# Arduino_Mega14x.net
KiCad netlist of a schematic drawn in EAGLE
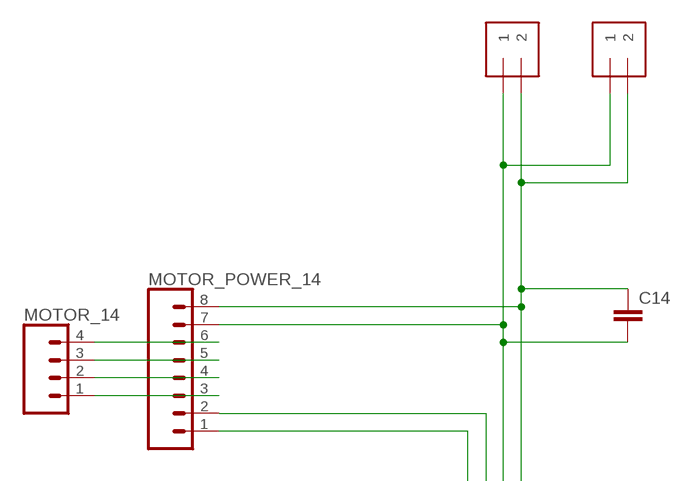
[diagram p0: schematic, sheet 1, part 1 of 3]
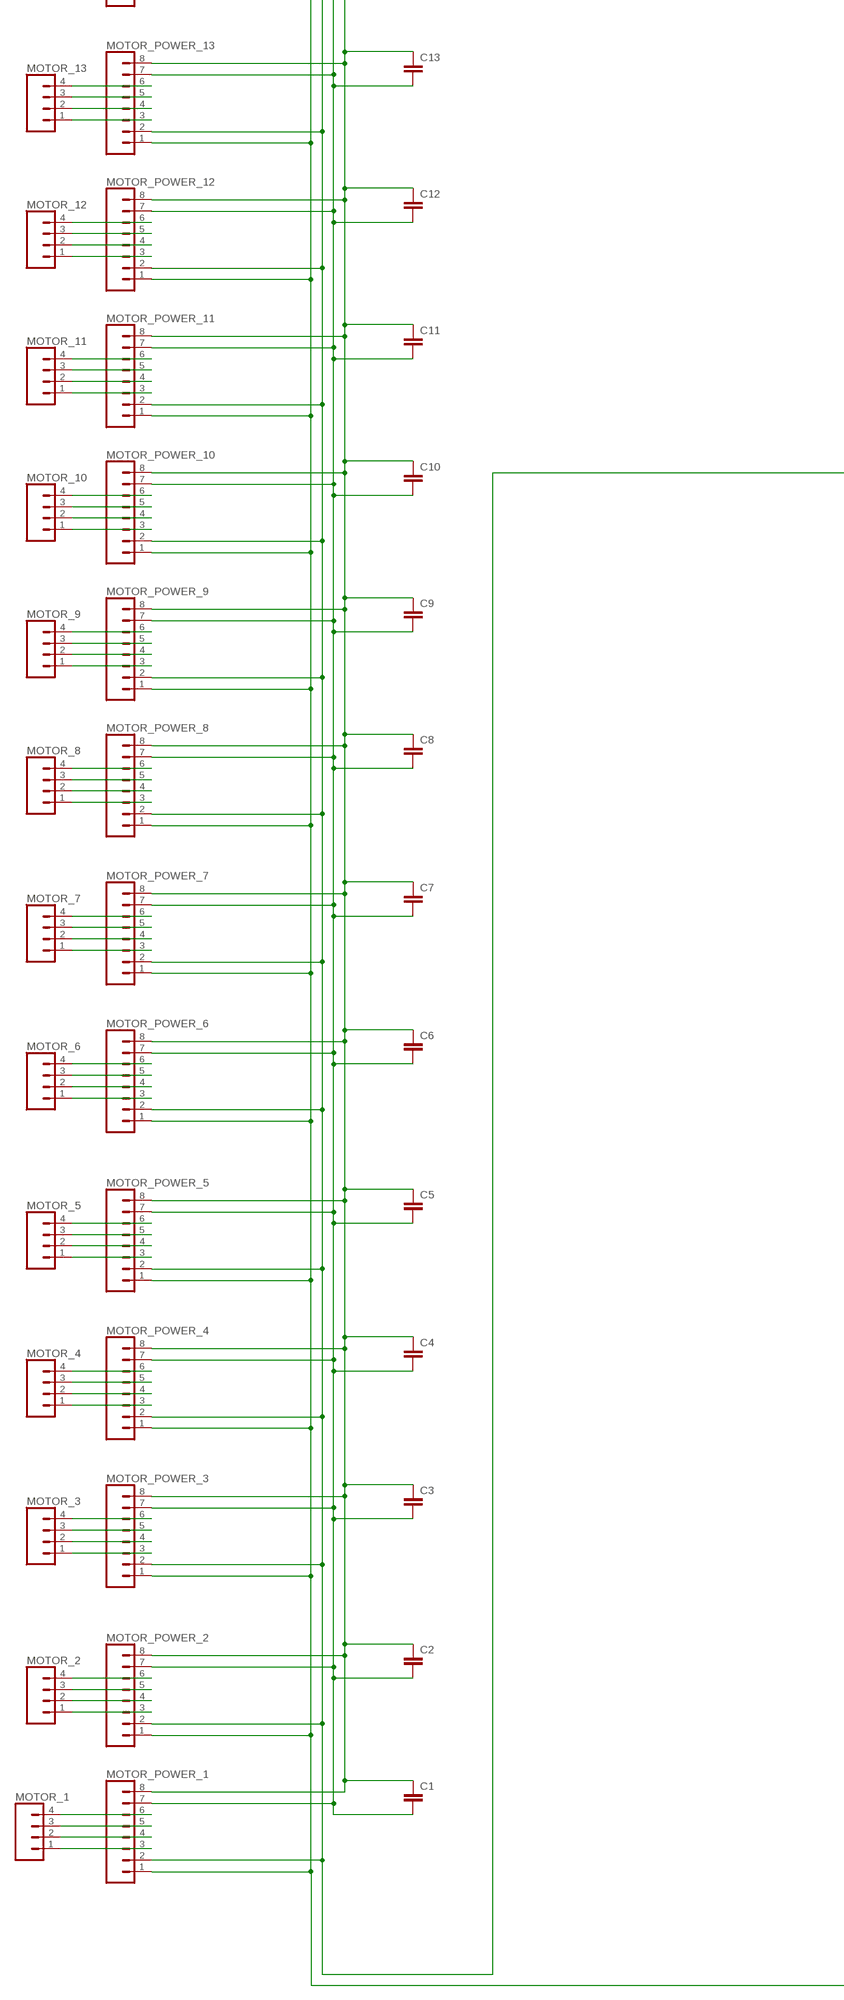
[diagram p1: schematic, sheet 1, part 2 of 3]
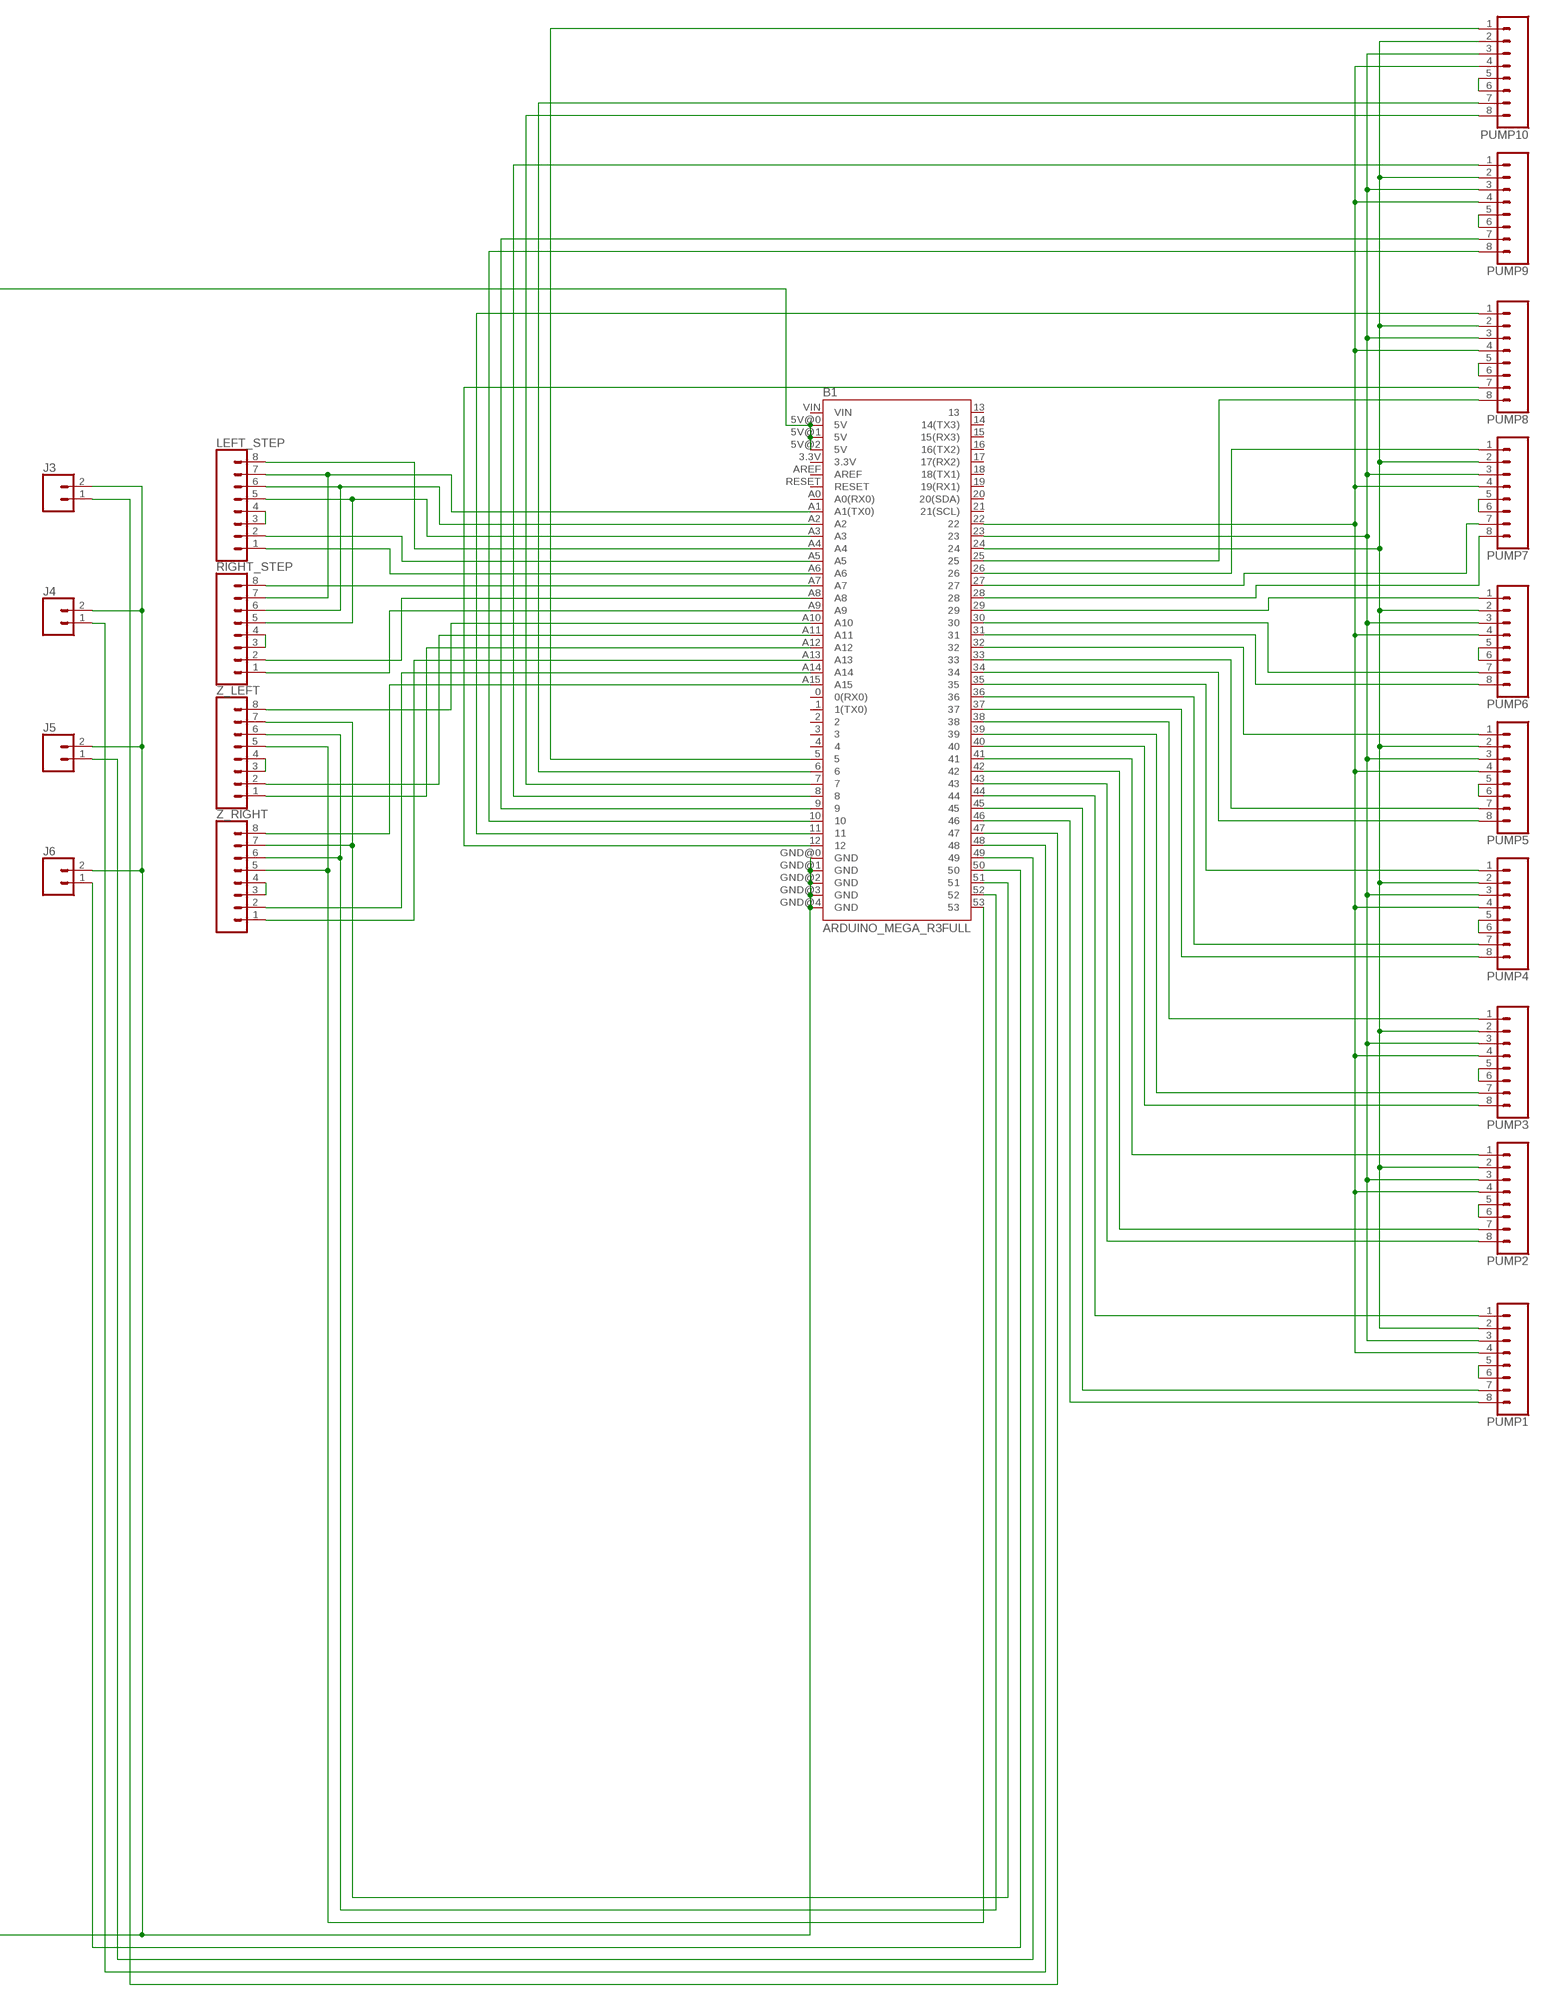
[diagram p2: schematic, sheet 1, part 3 of 3]

(export (version "E")
  (design (tool "Eeschema 10.0.6"))
  (components
    (comp (ref "B1")
      (value "ARDUINO_MEGA_R3FULL")
      (footprint "eagle-import:ARDUINO_MEGA")
      (libsource (lib "eagle-import") (part "ARDUINO_MEGA_R3FULL"))
    )
    (comp (ref "C1")
      (value "C5/2.5")
      (footprint "eagle-import:C5B2.5")
      (libsource (lib "eagle-import") (part "C5/2.5"))
    )
    (comp (ref "C2")
      (value "C5/2.5")
      (footprint "eagle-import:C5B2.5")
      (libsource (lib "eagle-import") (part "C5/2.5"))
    )
    (comp (ref "C3")
      (value "C5/2.5")
      (footprint "eagle-import:C5B2.5")
      (libsource (lib "eagle-import") (part "C5/2.5"))
    )
    (comp (ref "C4")
      (value "C5/2.5")
      (footprint "eagle-import:C5B2.5")
      (libsource (lib "eagle-import") (part "C5/2.5"))
    )
    (comp (ref "C5")
      (value "C5/2.5")
      (footprint "eagle-import:C5B2.5")
      (libsource (lib "eagle-import") (part "C5/2.5"))
    )
    (comp (ref "C6")
      (value "C5/2.5")
      (footprint "eagle-import:C5B2.5")
      (libsource (lib "eagle-import") (part "C5/2.5"))
    )
    (comp (ref "C7")
      (value "C5/2.5")
      (footprint "eagle-import:C5B2.5")
      (libsource (lib "eagle-import") (part "C5/2.5"))
    )
    (comp (ref "C8")
      (value "C5/2.5")
      (footprint "eagle-import:C5B2.5")
      (libsource (lib "eagle-import") (part "C5/2.5"))
    )
    (comp (ref "C9")
      (value "C5/2.5")
      (footprint "eagle-import:C5B2.5")
      (libsource (lib "eagle-import") (part "C5/2.5"))
    )
    (comp (ref "C10")
      (value "C5/2.5")
      (footprint "eagle-import:C5B2.5")
      (libsource (lib "eagle-import") (part "C5/2.5"))
    )
    (comp (ref "C11")
      (value "C5/2.5")
      (footprint "eagle-import:C5B2.5")
      (libsource (lib "eagle-import") (part "C5/2.5"))
    )
    (comp (ref "C12")
      (value "C5/2.5")
      (footprint "eagle-import:C5B2.5")
      (libsource (lib "eagle-import") (part "C5/2.5"))
    )
    (comp (ref "C13")
      (value "C5/2.5")
      (footprint "eagle-import:C5B2.5")
      (libsource (lib "eagle-import") (part "C5/2.5"))
    )
    (comp (ref "C14")
      (value "C5/2.5")
      (footprint "eagle-import:C5B2.5")
      (libsource (lib "eagle-import") (part "C5/2.5"))
    )
    (comp (ref "J1")
      (value "1X2-3.5MM")
      (footprint "eagle-import:1X2-3.5MM")
      (libsource (lib "eagle-import") (part "1X2-3.5MM"))
    )
    (comp (ref "J2")
      (value "1X2-3.5MM")
      (footprint "eagle-import:1X2-3.5MM")
      (libsource (lib "eagle-import") (part "1X2-3.5MM"))
    )
    (comp (ref "J3")
      (value "CONN_02")
      (footprint "eagle-import:1X02")
      (libsource (lib "eagle-import") (part "CONN_02"))
    )
    (comp (ref "J4")
      (value "CONN_02")
      (footprint "eagle-import:1X02")
      (libsource (lib "eagle-import") (part "CONN_02"))
    )
    (comp (ref "J5")
      (value "CONN_02")
      (footprint "eagle-import:1X02")
      (libsource (lib "eagle-import") (part "CONN_02"))
    )
    (comp (ref "J6")
      (value "CONN_02")
      (footprint "eagle-import:1X02")
      (libsource (lib "eagle-import") (part "CONN_02"))
    )
    (comp (ref "LEFT_STEP")
      (value "CONN_08\"")
      (footprint "eagle-import:1X08")
      (libsource (lib "eagle-import") (part "CONN_08{dblquote}"))
    )
    (comp (ref "MOTOR_1")
      (value "CONN_04")
      (footprint "eagle-import:1X04")
      (libsource (lib "eagle-import") (part "CONN_04"))
    )
    (comp (ref "MOTOR_2")
      (value "CONN_04")
      (footprint "eagle-import:1X04")
      (libsource (lib "eagle-import") (part "CONN_04"))
    )
    (comp (ref "MOTOR_3")
      (value "CONN_04")
      (footprint "eagle-import:1X04")
      (libsource (lib "eagle-import") (part "CONN_04"))
    )
    (comp (ref "MOTOR_4")
      (value "CONN_04")
      (footprint "eagle-import:1X04")
      (libsource (lib "eagle-import") (part "CONN_04"))
    )
    (comp (ref "MOTOR_5")
      (value "CONN_04")
      (footprint "eagle-import:1X04")
      (libsource (lib "eagle-import") (part "CONN_04"))
    )
    (comp (ref "MOTOR_6")
      (value "CONN_04")
      (footprint "eagle-import:1X04")
      (libsource (lib "eagle-import") (part "CONN_04"))
    )
    (comp (ref "MOTOR_7")
      (value "CONN_04")
      (footprint "eagle-import:1X04")
      (libsource (lib "eagle-import") (part "CONN_04"))
    )
    (comp (ref "MOTOR_8")
      (value "CONN_04")
      (footprint "eagle-import:1X04")
      (libsource (lib "eagle-import") (part "CONN_04"))
    )
    (comp (ref "MOTOR_9")
      (value "CONN_04")
      (footprint "eagle-import:1X04")
      (libsource (lib "eagle-import") (part "CONN_04"))
    )
    (comp (ref "MOTOR_10")
      (value "CONN_04")
      (footprint "eagle-import:1X04")
      (libsource (lib "eagle-import") (part "CONN_04"))
    )
    (comp (ref "MOTOR_11")
      (value "CONN_04")
      (footprint "eagle-import:1X04")
      (libsource (lib "eagle-import") (part "CONN_04"))
    )
    (comp (ref "MOTOR_12")
      (value "CONN_04")
      (footprint "eagle-import:1X04")
      (libsource (lib "eagle-import") (part "CONN_04"))
    )
    (comp (ref "MOTOR_13")
      (value "CONN_04")
      (footprint "eagle-import:1X04")
      (libsource (lib "eagle-import") (part "CONN_04"))
    )
    (comp (ref "MOTOR_14")
      (value "CONN_04")
      (footprint "eagle-import:1X04")
      (libsource (lib "eagle-import") (part "CONN_04"))
    )
    (comp (ref "MOTOR_POWER_1")
      (value "CONN_08\"")
      (footprint "eagle-import:1X08")
      (libsource (lib "eagle-import") (part "CONN_08{dblquote}"))
    )
    (comp (ref "MOTOR_POWER_2")
      (value "CONN_08\"")
      (footprint "eagle-import:1X08")
      (libsource (lib "eagle-import") (part "CONN_08{dblquote}"))
    )
    (comp (ref "MOTOR_POWER_3")
      (value "CONN_08\"")
      (footprint "eagle-import:1X08")
      (libsource (lib "eagle-import") (part "CONN_08{dblquote}"))
    )
    (comp (ref "MOTOR_POWER_4")
      (value "CONN_08\"")
      (footprint "eagle-import:1X08")
      (libsource (lib "eagle-import") (part "CONN_08{dblquote}"))
    )
    (comp (ref "MOTOR_POWER_5")
      (value "CONN_08\"")
      (footprint "eagle-import:1X08")
      (libsource (lib "eagle-import") (part "CONN_08{dblquote}"))
    )
    (comp (ref "MOTOR_POWER_6")
      (value "CONN_08\"")
      (footprint "eagle-import:1X08")
      (libsource (lib "eagle-import") (part "CONN_08{dblquote}"))
    )
    (comp (ref "MOTOR_POWER_7")
      (value "CONN_08\"")
      (footprint "eagle-import:1X08")
      (libsource (lib "eagle-import") (part "CONN_08{dblquote}"))
    )
    (comp (ref "MOTOR_POWER_8")
      (value "CONN_08\"")
      (footprint "eagle-import:1X08")
      (libsource (lib "eagle-import") (part "CONN_08{dblquote}"))
    )
    (comp (ref "MOTOR_POWER_9")
      (value "CONN_08\"")
      (footprint "eagle-import:1X08")
      (libsource (lib "eagle-import") (part "CONN_08{dblquote}"))
    )
    (comp (ref "MOTOR_POWER_10")
      (value "CONN_08\"")
      (footprint "eagle-import:1X08")
      (libsource (lib "eagle-import") (part "CONN_08{dblquote}"))
    )
    (comp (ref "MOTOR_POWER_11")
      (value "CONN_08\"")
      (footprint "eagle-import:1X08")
      (libsource (lib "eagle-import") (part "CONN_08{dblquote}"))
    )
    (comp (ref "MOTOR_POWER_12")
      (value "CONN_08\"")
      (footprint "eagle-import:1X08")
      (libsource (lib "eagle-import") (part "CONN_08{dblquote}"))
    )
    (comp (ref "MOTOR_POWER_13")
      (value "CONN_08\"")
      (footprint "eagle-import:1X08")
      (libsource (lib "eagle-import") (part "CONN_08{dblquote}"))
    )
    (comp (ref "MOTOR_POWER_14")
      (value "CONN_08\"")
      (footprint "eagle-import:1X08")
      (libsource (lib "eagle-import") (part "CONN_08{dblquote}"))
    )
    (comp (ref "PUMP1")
      (value "CONN_08\"")
      (footprint "eagle-import:1X08")
      (libsource (lib "eagle-import") (part "CONN_08{dblquote}"))
    )
    (comp (ref "PUMP2")
      (value "CONN_08\"")
      (footprint "eagle-import:1X08")
      (libsource (lib "eagle-import") (part "CONN_08{dblquote}"))
    )
    (comp (ref "PUMP3")
      (value "CONN_08\"")
      (footprint "eagle-import:1X08")
      (libsource (lib "eagle-import") (part "CONN_08{dblquote}"))
    )
    (comp (ref "PUMP4")
      (value "CONN_08\"")
      (footprint "eagle-import:1X08")
      (libsource (lib "eagle-import") (part "CONN_08{dblquote}"))
    )
    (comp (ref "PUMP5")
      (value "CONN_08\"")
      (footprint "eagle-import:1X08")
      (libsource (lib "eagle-import") (part "CONN_08{dblquote}"))
    )
    (comp (ref "PUMP6")
      (value "CONN_08\"")
      (footprint "eagle-import:1X08")
      (libsource (lib "eagle-import") (part "CONN_08{dblquote}"))
    )
    (comp (ref "PUMP7")
      (value "CONN_08\"")
      (footprint "eagle-import:1X08")
      (libsource (lib "eagle-import") (part "CONN_08{dblquote}"))
    )
    (comp (ref "PUMP8")
      (value "CONN_08\"")
      (footprint "eagle-import:1X08")
      (libsource (lib "eagle-import") (part "CONN_08{dblquote}"))
    )
    (comp (ref "PUMP9")
      (value "CONN_08\"")
      (footprint "eagle-import:1X08")
      (libsource (lib "eagle-import") (part "CONN_08{dblquote}"))
    )
    (comp (ref "PUMP10")
      (value "CONN_08\"")
      (footprint "eagle-import:1X08")
      (libsource (lib "eagle-import") (part "CONN_08{dblquote}"))
    )
    (comp (ref "RIGHT_STEP")
      (value "CONN_08\"")
      (footprint "eagle-import:1X08")
      (libsource (lib "eagle-import") (part "CONN_08{dblquote}"))
    )
    (comp (ref "Z_LEFT")
      (value "CONN_08\"")
      (footprint "eagle-import:1X08")
      (libsource (lib "eagle-import") (part "CONN_08{dblquote}"))
    )
    (comp (ref "Z_RIGHT")
      (value "CONN_08\"")
      (footprint "eagle-import:1X08")
      (libsource (lib "eagle-import") (part "CONN_08{dblquote}"))
    )
  )
  (nets
    (net (code "1") (name "Net-(B1-5V-Pad5V@0)") (class "Default")
      (node (ref "B1") (pin "5V@0") (pinfunction "5V_5V@0") (pintype "bidirectional"))
      (node (ref "B1") (pin "5V@1") (pinfunction "5V_5V@1") (pintype "bidirectional"))
      (node (ref "B1") (pin "5V@2") (pinfunction "5V_5V@2") (pintype "bidirectional"))
      (node (ref "MOTOR_POWER_1") (pin "2") (pinfunction "2_2") (pintype "passive"))
      (node (ref "MOTOR_POWER_10") (pin "2") (pinfunction "2_2") (pintype "passive"))
      (node (ref "MOTOR_POWER_11") (pin "2") (pinfunction "2_2") (pintype "passive"))
      (node (ref "MOTOR_POWER_12") (pin "2") (pinfunction "2_2") (pintype "passive"))
      (node (ref "MOTOR_POWER_13") (pin "2") (pinfunction "2_2") (pintype "passive"))
      (node (ref "MOTOR_POWER_14") (pin "2") (pinfunction "2_2") (pintype "passive"))
      (node (ref "MOTOR_POWER_2") (pin "2") (pinfunction "2_2") (pintype "passive"))
      (node (ref "MOTOR_POWER_3") (pin "2") (pinfunction "2_2") (pintype "passive"))
      (node (ref "MOTOR_POWER_4") (pin "2") (pinfunction "2_2") (pintype "passive"))
      (node (ref "MOTOR_POWER_5") (pin "2") (pinfunction "2_2") (pintype "passive"))
      (node (ref "MOTOR_POWER_6") (pin "2") (pinfunction "2_2") (pintype "passive"))
      (node (ref "MOTOR_POWER_7") (pin "2") (pinfunction "2_2") (pintype "passive"))
      (node (ref "MOTOR_POWER_8") (pin "2") (pinfunction "2_2") (pintype "passive"))
      (node (ref "MOTOR_POWER_9") (pin "2") (pinfunction "2_2") (pintype "passive"))
    )
    (net (code "2") (name "Net-(B1-A1(TX0))") (class "Default")
      (node (ref "B1") (pin "A1") (pinfunction "A1(TX0)_A1") (pintype "bidirectional"))
      (node (ref "LEFT_STEP") (pin "7") (pinfunction "7_7") (pintype "passive"))
      (node (ref "RIGHT_STEP") (pin "7") (pinfunction "7_7") (pintype "passive"))
    )
    (net (code "3") (name "Net-(B1-GND-PadGND@0)") (class "Default")
      (node (ref "B1") (pin "GND@0") (pinfunction "GND_GND@0") (pintype "bidirectional"))
      (node (ref "B1") (pin "GND@1") (pinfunction "GND_GND@1") (pintype "bidirectional"))
      (node (ref "B1") (pin "GND@2") (pinfunction "GND_GND@2") (pintype "bidirectional"))
      (node (ref "B1") (pin "GND@3") (pinfunction "GND_GND@3") (pintype "bidirectional"))
      (node (ref "B1") (pin "GND@4") (pinfunction "GND_GND@4") (pintype "bidirectional"))
      (node (ref "J3") (pin "2") (pinfunction "2_2") (pintype "passive"))
      (node (ref "J4") (pin "2") (pinfunction "2_2") (pintype "passive"))
      (node (ref "J5") (pin "2") (pinfunction "2_2") (pintype "passive"))
      (node (ref "J6") (pin "2") (pinfunction "2_2") (pintype "passive"))
      (node (ref "MOTOR_POWER_1") (pin "1") (pinfunction "1_1") (pintype "passive"))
      (node (ref "MOTOR_POWER_10") (pin "1") (pinfunction "1_1") (pintype "passive"))
      (node (ref "MOTOR_POWER_11") (pin "1") (pinfunction "1_1") (pintype "passive"))
      (node (ref "MOTOR_POWER_12") (pin "1") (pinfunction "1_1") (pintype "passive"))
      (node (ref "MOTOR_POWER_13") (pin "1") (pinfunction "1_1") (pintype "passive"))
      (node (ref "MOTOR_POWER_14") (pin "1") (pinfunction "1_1") (pintype "passive"))
      (node (ref "MOTOR_POWER_2") (pin "1") (pinfunction "1_1") (pintype "passive"))
      (node (ref "MOTOR_POWER_3") (pin "1") (pinfunction "1_1") (pintype "passive"))
      (node (ref "MOTOR_POWER_4") (pin "1") (pinfunction "1_1") (pintype "passive"))
      (node (ref "MOTOR_POWER_5") (pin "1") (pinfunction "1_1") (pintype "passive"))
      (node (ref "MOTOR_POWER_6") (pin "1") (pinfunction "1_1") (pintype "passive"))
      (node (ref "MOTOR_POWER_7") (pin "1") (pinfunction "1_1") (pintype "passive"))
      (node (ref "MOTOR_POWER_8") (pin "1") (pinfunction "1_1") (pintype "passive"))
      (node (ref "MOTOR_POWER_9") (pin "1") (pinfunction "1_1") (pintype "passive"))
    )
    (net (code "4") (name "Net-(B1-Pad5)") (class "Default")
      (node (ref "B1") (pin "5") (pinfunction "5_5") (pintype "bidirectional"))
      (node (ref "PUMP10") (pin "1") (pinfunction "1_1") (pintype "passive"))
    )
    (net (code "5") (name "Net-(B1-Pad6)") (class "Default")
      (node (ref "B1") (pin "6") (pinfunction "6_6") (pintype "bidirectional"))
      (node (ref "PUMP10") (pin "7") (pinfunction "7_7") (pintype "passive"))
    )
    (net (code "6") (name "Net-(B1-Pad7)") (class "Default")
      (node (ref "B1") (pin "7") (pinfunction "7_7") (pintype "bidirectional"))
      (node (ref "PUMP10") (pin "8") (pinfunction "8_8") (pintype "passive"))
    )
    (net (code "7") (name "Net-(B1-Pad8)") (class "Default")
      (node (ref "B1") (pin "8") (pinfunction "8_8") (pintype "bidirectional"))
      (node (ref "PUMP9") (pin "1") (pinfunction "1_1") (pintype "passive"))
    )
    (net (code "8") (name "Net-(B1-Pad9)") (class "Default")
      (node (ref "B1") (pin "9") (pinfunction "9_9") (pintype "bidirectional"))
      (node (ref "PUMP9") (pin "7") (pinfunction "7_7") (pintype "passive"))
    )
    (net (code "9") (name "Net-(B1-Pad10)") (class "Default")
      (node (ref "B1") (pin "10") (pinfunction "10_10") (pintype "bidirectional"))
      (node (ref "PUMP9") (pin "8") (pinfunction "8_8") (pintype "passive"))
    )
    (net (code "10") (name "Net-(B1-Pad11)") (class "Default")
      (node (ref "B1") (pin "11") (pinfunction "11_11") (pintype "bidirectional"))
      (node (ref "PUMP8") (pin "1") (pinfunction "1_1") (pintype "passive"))
    )
    (net (code "11") (name "Net-(B1-Pad12)") (class "Default")
      (node (ref "B1") (pin "12") (pinfunction "12_12") (pintype "bidirectional"))
      (node (ref "PUMP8") (pin "7") (pinfunction "7_7") (pintype "passive"))
    )
    (net (code "12") (name "Net-(B1-Pad22)") (class "Default")
      (node (ref "B1") (pin "22") (pinfunction "22_22") (pintype "bidirectional"))
      (node (ref "PUMP1") (pin "4") (pinfunction "4_4") (pintype "passive"))
      (node (ref "PUMP10") (pin "4") (pinfunction "4_4") (pintype "passive"))
      (node (ref "PUMP2") (pin "4") (pinfunction "4_4") (pintype "passive"))
      (node (ref "PUMP3") (pin "4") (pinfunction "4_4") (pintype "passive"))
      (node (ref "PUMP4") (pin "4") (pinfunction "4_4") (pintype "passive"))
      (node (ref "PUMP5") (pin "4") (pinfunction "4_4") (pintype "passive"))
      (node (ref "PUMP6") (pin "4") (pinfunction "4_4") (pintype "passive"))
      (node (ref "PUMP7") (pin "4") (pinfunction "4_4") (pintype "passive"))
      (node (ref "PUMP8") (pin "4") (pinfunction "4_4") (pintype "passive"))
      (node (ref "PUMP9") (pin "4") (pinfunction "4_4") (pintype "passive"))
    )
    (net (code "13") (name "Net-(B1-Pad23)") (class "Default")
      (node (ref "B1") (pin "23") (pinfunction "23_23") (pintype "bidirectional"))
      (node (ref "PUMP1") (pin "3") (pinfunction "3_3") (pintype "passive"))
      (node (ref "PUMP10") (pin "3") (pinfunction "3_3") (pintype "passive"))
      (node (ref "PUMP2") (pin "3") (pinfunction "3_3") (pintype "passive"))
      (node (ref "PUMP3") (pin "3") (pinfunction "3_3") (pintype "passive"))
      (node (ref "PUMP4") (pin "3") (pinfunction "3_3") (pintype "passive"))
      (node (ref "PUMP5") (pin "3") (pinfunction "3_3") (pintype "passive"))
      (node (ref "PUMP6") (pin "3") (pinfunction "3_3") (pintype "passive"))
      (node (ref "PUMP7") (pin "3") (pinfunction "3_3") (pintype "passive"))
      (node (ref "PUMP8") (pin "3") (pinfunction "3_3") (pintype "passive"))
      (node (ref "PUMP9") (pin "3") (pinfunction "3_3") (pintype "passive"))
    )
    (net (code "14") (name "Net-(B1-Pad24)") (class "Default")
      (node (ref "B1") (pin "24") (pinfunction "24_24") (pintype "bidirectional"))
      (node (ref "PUMP1") (pin "2") (pinfunction "2_2") (pintype "passive"))
      (node (ref "PUMP10") (pin "2") (pinfunction "2_2") (pintype "passive"))
      (node (ref "PUMP2") (pin "2") (pinfunction "2_2") (pintype "passive"))
      (node (ref "PUMP3") (pin "2") (pinfunction "2_2") (pintype "passive"))
      (node (ref "PUMP4") (pin "2") (pinfunction "2_2") (pintype "passive"))
      (node (ref "PUMP5") (pin "2") (pinfunction "2_2") (pintype "passive"))
      (node (ref "PUMP6") (pin "2") (pinfunction "2_2") (pintype "passive"))
      (node (ref "PUMP7") (pin "2") (pinfunction "2_2") (pintype "passive"))
      (node (ref "PUMP8") (pin "2") (pinfunction "2_2") (pintype "passive"))
      (node (ref "PUMP9") (pin "2") (pinfunction "2_2") (pintype "passive"))
    )
    (net (code "15") (name "Net-(B1-Pad25)") (class "Default")
      (node (ref "B1") (pin "25") (pinfunction "25_25") (pintype "bidirectional"))
      (node (ref "PUMP8") (pin "8") (pinfunction "8_8") (pintype "passive"))
    )
    (net (code "16") (name "Net-(B1-Pad26)") (class "Default")
      (node (ref "B1") (pin "26") (pinfunction "26_26") (pintype "bidirectional"))
      (node (ref "PUMP7") (pin "1") (pinfunction "1_1") (pintype "passive"))
    )
    (net (code "17") (name "Net-(B1-Pad27)") (class "Default")
      (node (ref "B1") (pin "27") (pinfunction "27_27") (pintype "bidirectional"))
      (node (ref "PUMP7") (pin "7") (pinfunction "7_7") (pintype "passive"))
    )
    (net (code "18") (name "Net-(B1-Pad28)") (class "Default")
      (node (ref "B1") (pin "28") (pinfunction "28_28") (pintype "bidirectional"))
      (node (ref "PUMP7") (pin "8") (pinfunction "8_8") (pintype "passive"))
    )
    (net (code "19") (name "Net-(B1-Pad29)") (class "Default")
      (node (ref "B1") (pin "29") (pinfunction "29_29") (pintype "bidirectional"))
      (node (ref "PUMP6") (pin "1") (pinfunction "1_1") (pintype "passive"))
    )
    (net (code "20") (name "Net-(B1-Pad30)") (class "Default")
      (node (ref "B1") (pin "30") (pinfunction "30_30") (pintype "bidirectional"))
      (node (ref "PUMP6") (pin "7") (pinfunction "7_7") (pintype "passive"))
    )
    (net (code "21") (name "Net-(B1-Pad31)") (class "Default")
      (node (ref "B1") (pin "31") (pinfunction "31_31") (pintype "bidirectional"))
      (node (ref "PUMP6") (pin "8") (pinfunction "8_8") (pintype "passive"))
    )
    (net (code "22") (name "Net-(B1-Pad32)") (class "Default")
      (node (ref "B1") (pin "32") (pinfunction "32_32") (pintype "bidirectional"))
      (node (ref "PUMP5") (pin "1") (pinfunction "1_1") (pintype "passive"))
    )
    (net (code "23") (name "Net-(B1-Pad33)") (class "Default")
      (node (ref "B1") (pin "33") (pinfunction "33_33") (pintype "bidirectional"))
      (node (ref "PUMP5") (pin "7") (pinfunction "7_7") (pintype "passive"))
    )
    (net (code "24") (name "Net-(B1-Pad34)") (class "Default")
      (node (ref "B1") (pin "34") (pinfunction "34_34") (pintype "bidirectional"))
      (node (ref "PUMP5") (pin "8") (pinfunction "8_8") (pintype "passive"))
    )
    (net (code "25") (name "Net-(B1-Pad35)") (class "Default")
      (node (ref "B1") (pin "35") (pinfunction "35_35") (pintype "bidirectional"))
      (node (ref "PUMP4") (pin "1") (pinfunction "1_1") (pintype "passive"))
    )
    (net (code "26") (name "Net-(B1-Pad36)") (class "Default")
      (node (ref "B1") (pin "36") (pinfunction "36_36") (pintype "bidirectional"))
      (node (ref "PUMP4") (pin "7") (pinfunction "7_7") (pintype "passive"))
    )
    (net (code "27") (name "Net-(B1-Pad37)") (class "Default")
      (node (ref "B1") (pin "37") (pinfunction "37_37") (pintype "bidirectional"))
      (node (ref "PUMP4") (pin "8") (pinfunction "8_8") (pintype "passive"))
    )
    (net (code "28") (name "Net-(B1-Pad38)") (class "Default")
      (node (ref "B1") (pin "38") (pinfunction "38_38") (pintype "bidirectional"))
      (node (ref "PUMP3") (pin "1") (pinfunction "1_1") (pintype "passive"))
    )
    (net (code "29") (name "Net-(B1-Pad39)") (class "Default")
      (node (ref "B1") (pin "39") (pinfunction "39_39") (pintype "bidirectional"))
      (node (ref "PUMP3") (pin "7") (pinfunction "7_7") (pintype "passive"))
    )
    (net (code "30") (name "Net-(B1-Pad40)") (class "Default")
      (node (ref "B1") (pin "40") (pinfunction "40_40") (pintype "bidirectional"))
      (node (ref "PUMP3") (pin "8") (pinfunction "8_8") (pintype "passive"))
    )
    (net (code "31") (name "Net-(B1-Pad41)") (class "Default")
      (node (ref "B1") (pin "41") (pinfunction "41_41") (pintype "bidirectional"))
      (node (ref "PUMP2") (pin "1") (pinfunction "1_1") (pintype "passive"))
    )
    (net (code "32") (name "Net-(B1-Pad42)") (class "Default")
      (node (ref "B1") (pin "42") (pinfunction "42_42") (pintype "bidirectional"))
      (node (ref "PUMP2") (pin "7") (pinfunction "7_7") (pintype "passive"))
    )
    (net (code "33") (name "Net-(B1-Pad43)") (class "Default")
      (node (ref "B1") (pin "43") (pinfunction "43_43") (pintype "bidirectional"))
      (node (ref "PUMP2") (pin "8") (pinfunction "8_8") (pintype "passive"))
    )
    (net (code "34") (name "Net-(B1-Pad44)") (class "Default")
      (node (ref "B1") (pin "44") (pinfunction "44_44") (pintype "bidirectional"))
      (node (ref "PUMP1") (pin "1") (pinfunction "1_1") (pintype "passive"))
    )
    (net (code "35") (name "Net-(B1-Pad45)") (class "Default")
      (node (ref "B1") (pin "45") (pinfunction "45_45") (pintype "bidirectional"))
      (node (ref "PUMP1") (pin "7") (pinfunction "7_7") (pintype "passive"))
    )
    (net (code "36") (name "Net-(B1-Pad46)") (class "Default")
      (node (ref "B1") (pin "46") (pinfunction "46_46") (pintype "bidirectional"))
      (node (ref "PUMP1") (pin "8") (pinfunction "8_8") (pintype "passive"))
    )
    (net (code "37") (name "Net-(B1-Pad47)") (class "Default")
      (node (ref "B1") (pin "47") (pinfunction "47_47") (pintype "bidirectional"))
      (node (ref "J3") (pin "1") (pinfunction "1_1") (pintype "passive"))
    )
    (net (code "38") (name "Net-(B1-Pad48)") (class "Default")
      (node (ref "B1") (pin "48") (pinfunction "48_48") (pintype "bidirectional"))
      (node (ref "J4") (pin "1") (pinfunction "1_1") (pintype "passive"))
    )
    (net (code "39") (name "Net-(B1-Pad49)") (class "Default")
      (node (ref "B1") (pin "49") (pinfunction "49_49") (pintype "bidirectional"))
      (node (ref "J5") (pin "1") (pinfunction "1_1") (pintype "passive"))
    )
    (net (code "40") (name "Net-(B1-Pad50)") (class "Default")
      (node (ref "B1") (pin "50") (pinfunction "50_50") (pintype "bidirectional"))
      (node (ref "J6") (pin "1") (pinfunction "1_1") (pintype "passive"))
    )
    (net (code "41") (name "Net-(B1-Pad51)") (class "Default")
      (node (ref "B1") (pin "51") (pinfunction "51_51") (pintype "bidirectional"))
      (node (ref "Z_LEFT") (pin "7") (pinfunction "7_7") (pintype "passive"))
      (node (ref "Z_RIGHT") (pin "7") (pinfunction "7_7") (pintype "passive"))
    )
    (net (code "42") (name "Net-(B1-Pad52)") (class "Default")
      (node (ref "B1") (pin "52") (pinfunction "52_52") (pintype "bidirectional"))
      (node (ref "Z_LEFT") (pin "6") (pinfunction "6_6") (pintype "passive"))
      (node (ref "Z_RIGHT") (pin "6") (pinfunction "6_6") (pintype "passive"))
    )
    (net (code "43") (name "Net-(B1-Pad53)") (class "Default")
      (node (ref "B1") (pin "53") (pinfunction "53_53") (pintype "bidirectional"))
      (node (ref "Z_LEFT") (pin "5") (pinfunction "5_5") (pintype "passive"))
      (node (ref "Z_RIGHT") (pin "5") (pinfunction "5_5") (pintype "passive"))
    )
    (net (code "44") (name "Net-(B1-PadA2)") (class "Default")
      (node (ref "B1") (pin "A2") (pinfunction "A2_A2") (pintype "bidirectional"))
      (node (ref "LEFT_STEP") (pin "6") (pinfunction "6_6") (pintype "passive"))
      (node (ref "RIGHT_STEP") (pin "6") (pinfunction "6_6") (pintype "passive"))
    )
    (net (code "45") (name "Net-(B1-PadA3)") (class "Default")
      (node (ref "B1") (pin "A3") (pinfunction "A3_A3") (pintype "bidirectional"))
      (node (ref "LEFT_STEP") (pin "5") (pinfunction "5_5") (pintype "passive"))
      (node (ref "RIGHT_STEP") (pin "5") (pinfunction "5_5") (pintype "passive"))
    )
    (net (code "46") (name "Net-(B1-PadA4)") (class "Default")
      (node (ref "B1") (pin "A4") (pinfunction "A4_A4") (pintype "bidirectional"))
      (node (ref "LEFT_STEP") (pin "8") (pinfunction "8_8") (pintype "passive"))
    )
    (net (code "47") (name "Net-(B1-PadA5)") (class "Default")
      (node (ref "B1") (pin "A5") (pinfunction "A5_A5") (pintype "bidirectional"))
      (node (ref "LEFT_STEP") (pin "2") (pinfunction "2_2") (pintype "passive"))
    )
    (net (code "48") (name "Net-(B1-PadA6)") (class "Default")
      (node (ref "B1") (pin "A6") (pinfunction "A6_A6") (pintype "bidirectional"))
      (node (ref "LEFT_STEP") (pin "1") (pinfunction "1_1") (pintype "passive"))
    )
    (net (code "49") (name "Net-(B1-PadA7)") (class "Default")
      (node (ref "B1") (pin "A7") (pinfunction "A7_A7") (pintype "bidirectional"))
      (node (ref "RIGHT_STEP") (pin "8") (pinfunction "8_8") (pintype "passive"))
    )
    (net (code "50") (name "Net-(B1-PadA8)") (class "Default")
      (node (ref "B1") (pin "A8") (pinfunction "A8_A8") (pintype "bidirectional"))
      (node (ref "RIGHT_STEP") (pin "2") (pinfunction "2_2") (pintype "passive"))
    )
    (net (code "51") (name "Net-(B1-PadA9)") (class "Default")
      (node (ref "B1") (pin "A9") (pinfunction "A9_A9") (pintype "bidirectional"))
      (node (ref "RIGHT_STEP") (pin "1") (pinfunction "1_1") (pintype "passive"))
    )
    (net (code "52") (name "Net-(B1-PadA10)") (class "Default")
      (node (ref "B1") (pin "A10") (pinfunction "A10_A10") (pintype "bidirectional"))
      (node (ref "Z_LEFT") (pin "8") (pinfunction "8_8") (pintype "passive"))
    )
    (net (code "53") (name "Net-(B1-PadA11)") (class "Default")
      (node (ref "B1") (pin "A11") (pinfunction "A11_A11") (pintype "bidirectional"))
      (node (ref "Z_LEFT") (pin "2") (pinfunction "2_2") (pintype "passive"))
    )
    (net (code "54") (name "Net-(B1-PadA12)") (class "Default")
      (node (ref "B1") (pin "A12") (pinfunction "A12_A12") (pintype "bidirectional"))
      (node (ref "Z_LEFT") (pin "1") (pinfunction "1_1") (pintype "passive"))
    )
    (net (code "55") (name "Net-(B1-PadA13)") (class "Default")
      (node (ref "B1") (pin "A13") (pinfunction "A13_A13") (pintype "bidirectional"))
      (node (ref "Z_RIGHT") (pin "1") (pinfunction "1_1") (pintype "passive"))
    )
    (net (code "56") (name "Net-(B1-PadA14)") (class "Default")
      (node (ref "B1") (pin "A14") (pinfunction "A14_A14") (pintype "bidirectional"))
      (node (ref "Z_RIGHT") (pin "2") (pinfunction "2_2") (pintype "passive"))
    )
    (net (code "57") (name "Net-(B1-PadA15)") (class "Default")
      (node (ref "B1") (pin "A15") (pinfunction "A15_A15") (pintype "bidirectional"))
      (node (ref "Z_RIGHT") (pin "8") (pinfunction "8_8") (pintype "passive"))
    )
    (net (code "58") (name "Net-(C1-Pad1)") (class "Default")
      (node (ref "C1") (pin "1") (pinfunction "1_1") (pintype "passive"))
      (node (ref "C10") (pin "1") (pinfunction "1_1") (pintype "passive"))
      (node (ref "C11") (pin "1") (pinfunction "1_1") (pintype "passive"))
      (node (ref "C12") (pin "1") (pinfunction "1_1") (pintype "passive"))
      (node (ref "C13") (pin "1") (pinfunction "1_1") (pintype "passive"))
      (node (ref "C14") (pin "1") (pinfunction "1_1") (pintype "passive"))
      (node (ref "C2") (pin "1") (pinfunction "1_1") (pintype "passive"))
      (node (ref "C3") (pin "1") (pinfunction "1_1") (pintype "passive"))
      (node (ref "C4") (pin "1") (pinfunction "1_1") (pintype "passive"))
      (node (ref "C5") (pin "1") (pinfunction "1_1") (pintype "passive"))
      (node (ref "C6") (pin "1") (pinfunction "1_1") (pintype "passive"))
      (node (ref "C7") (pin "1") (pinfunction "1_1") (pintype "passive"))
      (node (ref "C8") (pin "1") (pinfunction "1_1") (pintype "passive"))
      (node (ref "C9") (pin "1") (pinfunction "1_1") (pintype "passive"))
      (node (ref "J1") (pin "2") (pinfunction "2_2") (pintype "passive"))
      (node (ref "J2") (pin "2") (pinfunction "2_2") (pintype "passive"))
      (node (ref "MOTOR_POWER_1") (pin "8") (pinfunction "8_8") (pintype "passive"))
      (node (ref "MOTOR_POWER_10") (pin "8") (pinfunction "8_8") (pintype "passive"))
      (node (ref "MOTOR_POWER_11") (pin "8") (pinfunction "8_8") (pintype "passive"))
      (node (ref "MOTOR_POWER_12") (pin "8") (pinfunction "8_8") (pintype "passive"))
      (node (ref "MOTOR_POWER_13") (pin "8") (pinfunction "8_8") (pintype "passive"))
      (node (ref "MOTOR_POWER_14") (pin "8") (pinfunction "8_8") (pintype "passive"))
      (node (ref "MOTOR_POWER_2") (pin "8") (pinfunction "8_8") (pintype "passive"))
      (node (ref "MOTOR_POWER_3") (pin "8") (pinfunction "8_8") (pintype "passive"))
      (node (ref "MOTOR_POWER_4") (pin "8") (pinfunction "8_8") (pintype "passive"))
      (node (ref "MOTOR_POWER_5") (pin "8") (pinfunction "8_8") (pintype "passive"))
      (node (ref "MOTOR_POWER_6") (pin "8") (pinfunction "8_8") (pintype "passive"))
      (node (ref "MOTOR_POWER_7") (pin "8") (pinfunction "8_8") (pintype "passive"))
      (node (ref "MOTOR_POWER_8") (pin "8") (pinfunction "8_8") (pintype "passive"))
      (node (ref "MOTOR_POWER_9") (pin "8") (pinfunction "8_8") (pintype "passive"))
    )
    (net (code "59") (name "Net-(C1-Pad2)") (class "Default")
      (node (ref "C1") (pin "2") (pinfunction "2_2") (pintype "passive"))
      (node (ref "C10") (pin "2") (pinfunction "2_2") (pintype "passive"))
      (node (ref "C11") (pin "2") (pinfunction "2_2") (pintype "passive"))
      (node (ref "C12") (pin "2") (pinfunction "2_2") (pintype "passive"))
      (node (ref "C13") (pin "2") (pinfunction "2_2") (pintype "passive"))
      (node (ref "C14") (pin "2") (pinfunction "2_2") (pintype "passive"))
      (node (ref "C2") (pin "2") (pinfunction "2_2") (pintype "passive"))
      (node (ref "C3") (pin "2") (pinfunction "2_2") (pintype "passive"))
      (node (ref "C4") (pin "2") (pinfunction "2_2") (pintype "passive"))
      (node (ref "C5") (pin "2") (pinfunction "2_2") (pintype "passive"))
      (node (ref "C6") (pin "2") (pinfunction "2_2") (pintype "passive"))
      (node (ref "C7") (pin "2") (pinfunction "2_2") (pintype "passive"))
      (node (ref "C8") (pin "2") (pinfunction "2_2") (pintype "passive"))
      (node (ref "C9") (pin "2") (pinfunction "2_2") (pintype "passive"))
      (node (ref "J1") (pin "1") (pinfunction "1_1") (pintype "passive"))
      (node (ref "J2") (pin "1") (pinfunction "1_1") (pintype "passive"))
      (node (ref "MOTOR_POWER_1") (pin "7") (pinfunction "7_7") (pintype "passive"))
      (node (ref "MOTOR_POWER_10") (pin "7") (pinfunction "7_7") (pintype "passive"))
      (node (ref "MOTOR_POWER_11") (pin "7") (pinfunction "7_7") (pintype "passive"))
      (node (ref "MOTOR_POWER_12") (pin "7") (pinfunction "7_7") (pintype "passive"))
      (node (ref "MOTOR_POWER_13") (pin "7") (pinfunction "7_7") (pintype "passive"))
      (node (ref "MOTOR_POWER_14") (pin "7") (pinfunction "7_7") (pintype "passive"))
      (node (ref "MOTOR_POWER_2") (pin "7") (pinfunction "7_7") (pintype "passive"))
      (node (ref "MOTOR_POWER_3") (pin "7") (pinfunction "7_7") (pintype "passive"))
      (node (ref "MOTOR_POWER_4") (pin "7") (pinfunction "7_7") (pintype "passive"))
      (node (ref "MOTOR_POWER_5") (pin "7") (pinfunction "7_7") (pintype "passive"))
      (node (ref "MOTOR_POWER_6") (pin "7") (pinfunction "7_7") (pintype "passive"))
      (node (ref "MOTOR_POWER_7") (pin "7") (pinfunction "7_7") (pintype "passive"))
      (node (ref "MOTOR_POWER_8") (pin "7") (pinfunction "7_7") (pintype "passive"))
      (node (ref "MOTOR_POWER_9") (pin "7") (pinfunction "7_7") (pintype "passive"))
    )
    (net (code "60") (name "Net-(LEFT_STEP-Pad3)") (class "Default")
      (node (ref "LEFT_STEP") (pin "3") (pinfunction "3_3") (pintype "passive"))
      (node (ref "LEFT_STEP") (pin "4") (pinfunction "4_4") (pintype "passive"))
    )
    (net (code "61") (name "Net-(MOTOR_1-Pad1)") (class "Default")
      (node (ref "MOTOR_1") (pin "1") (pinfunction "1_1") (pintype "passive"))
      (node (ref "MOTOR_POWER_1") (pin "3") (pinfunction "3_3") (pintype "passive"))
    )
    (net (code "62") (name "Net-(MOTOR_1-Pad2)") (class "Default")
      (node (ref "MOTOR_1") (pin "2") (pinfunction "2_2") (pintype "passive"))
      (node (ref "MOTOR_POWER_1") (pin "4") (pinfunction "4_4") (pintype "passive"))
    )
    (net (code "63") (name "Net-(MOTOR_1-Pad3)") (class "Default")
      (node (ref "MOTOR_1") (pin "3") (pinfunction "3_3") (pintype "passive"))
      (node (ref "MOTOR_POWER_1") (pin "5") (pinfunction "5_5") (pintype "passive"))
    )
    (net (code "64") (name "Net-(MOTOR_1-Pad4)") (class "Default")
      (node (ref "MOTOR_1") (pin "4") (pinfunction "4_4") (pintype "passive"))
      (node (ref "MOTOR_POWER_1") (pin "6") (pinfunction "6_6") (pintype "passive"))
    )
    (net (code "65") (name "Net-(MOTOR_2-Pad1)") (class "Default")
      (node (ref "MOTOR_2") (pin "1") (pinfunction "1_1") (pintype "passive"))
      (node (ref "MOTOR_POWER_2") (pin "3") (pinfunction "3_3") (pintype "passive"))
    )
    (net (code "66") (name "Net-(MOTOR_2-Pad2)") (class "Default")
      (node (ref "MOTOR_2") (pin "2") (pinfunction "2_2") (pintype "passive"))
      (node (ref "MOTOR_POWER_2") (pin "4") (pinfunction "4_4") (pintype "passive"))
    )
    (net (code "67") (name "Net-(MOTOR_2-Pad3)") (class "Default")
      (node (ref "MOTOR_2") (pin "3") (pinfunction "3_3") (pintype "passive"))
      (node (ref "MOTOR_POWER_2") (pin "5") (pinfunction "5_5") (pintype "passive"))
    )
    (net (code "68") (name "Net-(MOTOR_2-Pad4)") (class "Default")
      (node (ref "MOTOR_2") (pin "4") (pinfunction "4_4") (pintype "passive"))
      (node (ref "MOTOR_POWER_2") (pin "6") (pinfunction "6_6") (pintype "passive"))
    )
    (net (code "69") (name "Net-(MOTOR_3-Pad1)") (class "Default")
      (node (ref "MOTOR_3") (pin "1") (pinfunction "1_1") (pintype "passive"))
      (node (ref "MOTOR_POWER_3") (pin "3") (pinfunction "3_3") (pintype "passive"))
    )
    (net (code "70") (name "Net-(MOTOR_3-Pad2)") (class "Default")
      (node (ref "MOTOR_3") (pin "2") (pinfunction "2_2") (pintype "passive"))
      (node (ref "MOTOR_POWER_3") (pin "4") (pinfunction "4_4") (pintype "passive"))
    )
    (net (code "71") (name "Net-(MOTOR_3-Pad3)") (class "Default")
      (node (ref "MOTOR_3") (pin "3") (pinfunction "3_3") (pintype "passive"))
      (node (ref "MOTOR_POWER_3") (pin "5") (pinfunction "5_5") (pintype "passive"))
    )
    (net (code "72") (name "Net-(MOTOR_3-Pad4)") (class "Default")
      (node (ref "MOTOR_3") (pin "4") (pinfunction "4_4") (pintype "passive"))
      (node (ref "MOTOR_POWER_3") (pin "6") (pinfunction "6_6") (pintype "passive"))
    )
    (net (code "73") (name "Net-(MOTOR_4-Pad1)") (class "Default")
      (node (ref "MOTOR_4") (pin "1") (pinfunction "1_1") (pintype "passive"))
      (node (ref "MOTOR_POWER_4") (pin "3") (pinfunction "3_3") (pintype "passive"))
    )
    (net (code "74") (name "Net-(MOTOR_4-Pad2)") (class "Default")
      (node (ref "MOTOR_4") (pin "2") (pinfunction "2_2") (pintype "passive"))
      (node (ref "MOTOR_POWER_4") (pin "4") (pinfunction "4_4") (pintype "passive"))
    )
    (net (code "75") (name "Net-(MOTOR_4-Pad3)") (class "Default")
      (node (ref "MOTOR_4") (pin "3") (pinfunction "3_3") (pintype "passive"))
      (node (ref "MOTOR_POWER_4") (pin "5") (pinfunction "5_5") (pintype "passive"))
    )
    (net (code "76") (name "Net-(MOTOR_4-Pad4)") (class "Default")
      (node (ref "MOTOR_4") (pin "4") (pinfunction "4_4") (pintype "passive"))
      (node (ref "MOTOR_POWER_4") (pin "6") (pinfunction "6_6") (pintype "passive"))
    )
    (net (code "77") (name "Net-(MOTOR_5-Pad1)") (class "Default")
      (node (ref "MOTOR_5") (pin "1") (pinfunction "1_1") (pintype "passive"))
      (node (ref "MOTOR_POWER_5") (pin "3") (pinfunction "3_3") (pintype "passive"))
    )
    (net (code "78") (name "Net-(MOTOR_5-Pad2)") (class "Default")
      (node (ref "MOTOR_5") (pin "2") (pinfunction "2_2") (pintype "passive"))
      (node (ref "MOTOR_POWER_5") (pin "4") (pinfunction "4_4") (pintype "passive"))
    )
    (net (code "79") (name "Net-(MOTOR_5-Pad3)") (class "Default")
      (node (ref "MOTOR_5") (pin "3") (pinfunction "3_3") (pintype "passive"))
      (node (ref "MOTOR_POWER_5") (pin "5") (pinfunction "5_5") (pintype "passive"))
    )
    (net (code "80") (name "Net-(MOTOR_5-Pad4)") (class "Default")
      (node (ref "MOTOR_5") (pin "4") (pinfunction "4_4") (pintype "passive"))
      (node (ref "MOTOR_POWER_5") (pin "6") (pinfunction "6_6") (pintype "passive"))
    )
    (net (code "81") (name "Net-(MOTOR_6-Pad1)") (class "Default")
      (node (ref "MOTOR_6") (pin "1") (pinfunction "1_1") (pintype "passive"))
      (node (ref "MOTOR_POWER_6") (pin "3") (pinfunction "3_3") (pintype "passive"))
    )
    (net (code "82") (name "Net-(MOTOR_6-Pad2)") (class "Default")
      (node (ref "MOTOR_6") (pin "2") (pinfunction "2_2") (pintype "passive"))
      (node (ref "MOTOR_POWER_6") (pin "4") (pinfunction "4_4") (pintype "passive"))
    )
    (net (code "83") (name "Net-(MOTOR_6-Pad3)") (class "Default")
      (node (ref "MOTOR_6") (pin "3") (pinfunction "3_3") (pintype "passive"))
      (node (ref "MOTOR_POWER_6") (pin "5") (pinfunction "5_5") (pintype "passive"))
    )
    (net (code "84") (name "Net-(MOTOR_6-Pad4)") (class "Default")
      (node (ref "MOTOR_6") (pin "4") (pinfunction "4_4") (pintype "passive"))
      (node (ref "MOTOR_POWER_6") (pin "6") (pinfunction "6_6") (pintype "passive"))
    )
    (net (code "85") (name "Net-(MOTOR_7-Pad1)") (class "Default")
      (node (ref "MOTOR_7") (pin "1") (pinfunction "1_1") (pintype "passive"))
      (node (ref "MOTOR_POWER_7") (pin "3") (pinfunction "3_3") (pintype "passive"))
    )
    (net (code "86") (name "Net-(MOTOR_7-Pad2)") (class "Default")
      (node (ref "MOTOR_7") (pin "2") (pinfunction "2_2") (pintype "passive"))
      (node (ref "MOTOR_POWER_7") (pin "4") (pinfunction "4_4") (pintype "passive"))
    )
    (net (code "87") (name "Net-(MOTOR_7-Pad3)") (class "Default")
      (node (ref "MOTOR_7") (pin "3") (pinfunction "3_3") (pintype "passive"))
      (node (ref "MOTOR_POWER_7") (pin "5") (pinfunction "5_5") (pintype "passive"))
    )
    (net (code "88") (name "Net-(MOTOR_7-Pad4)") (class "Default")
      (node (ref "MOTOR_7") (pin "4") (pinfunction "4_4") (pintype "passive"))
      (node (ref "MOTOR_POWER_7") (pin "6") (pinfunction "6_6") (pintype "passive"))
    )
    (net (code "89") (name "Net-(MOTOR_8-Pad1)") (class "Default")
      (node (ref "MOTOR_8") (pin "1") (pinfunction "1_1") (pintype "passive"))
      (node (ref "MOTOR_POWER_8") (pin "3") (pinfunction "3_3") (pintype "passive"))
    )
    (net (code "90") (name "Net-(MOTOR_8-Pad2)") (class "Default")
      (node (ref "MOTOR_8") (pin "2") (pinfunction "2_2") (pintype "passive"))
      (node (ref "MOTOR_POWER_8") (pin "4") (pinfunction "4_4") (pintype "passive"))
    )
    (net (code "91") (name "Net-(MOTOR_8-Pad3)") (class "Default")
      (node (ref "MOTOR_8") (pin "3") (pinfunction "3_3") (pintype "passive"))
      (node (ref "MOTOR_POWER_8") (pin "5") (pinfunction "5_5") (pintype "passive"))
    )
    (net (code "92") (name "Net-(MOTOR_8-Pad4)") (class "Default")
      (node (ref "MOTOR_8") (pin "4") (pinfunction "4_4") (pintype "passive"))
      (node (ref "MOTOR_POWER_8") (pin "6") (pinfunction "6_6") (pintype "passive"))
    )
    (net (code "93") (name "Net-(MOTOR_9-Pad1)") (class "Default")
      (node (ref "MOTOR_9") (pin "1") (pinfunction "1_1") (pintype "passive"))
      (node (ref "MOTOR_POWER_9") (pin "3") (pinfunction "3_3") (pintype "passive"))
    )
    (net (code "94") (name "Net-(MOTOR_9-Pad2)") (class "Default")
      (node (ref "MOTOR_9") (pin "2") (pinfunction "2_2") (pintype "passive"))
      (node (ref "MOTOR_POWER_9") (pin "4") (pinfunction "4_4") (pintype "passive"))
    )
    (net (code "95") (name "Net-(MOTOR_9-Pad3)") (class "Default")
      (node (ref "MOTOR_9") (pin "3") (pinfunction "3_3") (pintype "passive"))
      (node (ref "MOTOR_POWER_9") (pin "5") (pinfunction "5_5") (pintype "passive"))
    )
    (net (code "96") (name "Net-(MOTOR_9-Pad4)") (class "Default")
      (node (ref "MOTOR_9") (pin "4") (pinfunction "4_4") (pintype "passive"))
      (node (ref "MOTOR_POWER_9") (pin "6") (pinfunction "6_6") (pintype "passive"))
    )
    (net (code "97") (name "Net-(MOTOR_10-Pad1)") (class "Default")
      (node (ref "MOTOR_10") (pin "1") (pinfunction "1_1") (pintype "passive"))
      (node (ref "MOTOR_POWER_10") (pin "3") (pinfunction "3_3") (pintype "passive"))
    )
    (net (code "98") (name "Net-(MOTOR_10-Pad2)") (class "Default")
      (node (ref "MOTOR_10") (pin "2") (pinfunction "2_2") (pintype "passive"))
      (node (ref "MOTOR_POWER_10") (pin "4") (pinfunction "4_4") (pintype "passive"))
    )
    (net (code "99") (name "Net-(MOTOR_10-Pad3)") (class "Default")
      (node (ref "MOTOR_10") (pin "3") (pinfunction "3_3") (pintype "passive"))
      (node (ref "MOTOR_POWER_10") (pin "5") (pinfunction "5_5") (pintype "passive"))
    )
    (net (code "100") (name "Net-(MOTOR_10-Pad4)") (class "Default")
      (node (ref "MOTOR_10") (pin "4") (pinfunction "4_4") (pintype "passive"))
      (node (ref "MOTOR_POWER_10") (pin "6") (pinfunction "6_6") (pintype "passive"))
    )
    (net (code "101") (name "Net-(MOTOR_11-Pad1)") (class "Default")
      (node (ref "MOTOR_11") (pin "1") (pinfunction "1_1") (pintype "passive"))
      (node (ref "MOTOR_POWER_11") (pin "3") (pinfunction "3_3") (pintype "passive"))
    )
    (net (code "102") (name "Net-(MOTOR_11-Pad2)") (class "Default")
      (node (ref "MOTOR_11") (pin "2") (pinfunction "2_2") (pintype "passive"))
      (node (ref "MOTOR_POWER_11") (pin "4") (pinfunction "4_4") (pintype "passive"))
    )
    (net (code "103") (name "Net-(MOTOR_11-Pad3)") (class "Default")
      (node (ref "MOTOR_11") (pin "3") (pinfunction "3_3") (pintype "passive"))
      (node (ref "MOTOR_POWER_11") (pin "5") (pinfunction "5_5") (pintype "passive"))
    )
    (net (code "104") (name "Net-(MOTOR_11-Pad4)") (class "Default")
      (node (ref "MOTOR_11") (pin "4") (pinfunction "4_4") (pintype "passive"))
      (node (ref "MOTOR_POWER_11") (pin "6") (pinfunction "6_6") (pintype "passive"))
    )
    (net (code "105") (name "Net-(MOTOR_12-Pad1)") (class "Default")
      (node (ref "MOTOR_12") (pin "1") (pinfunction "1_1") (pintype "passive"))
      (node (ref "MOTOR_POWER_12") (pin "3") (pinfunction "3_3") (pintype "passive"))
    )
    (net (code "106") (name "Net-(MOTOR_12-Pad2)") (class "Default")
      (node (ref "MOTOR_12") (pin "2") (pinfunction "2_2") (pintype "passive"))
      (node (ref "MOTOR_POWER_12") (pin "4") (pinfunction "4_4") (pintype "passive"))
    )
    (net (code "107") (name "Net-(MOTOR_12-Pad3)") (class "Default")
      (node (ref "MOTOR_12") (pin "3") (pinfunction "3_3") (pintype "passive"))
      (node (ref "MOTOR_POWER_12") (pin "5") (pinfunction "5_5") (pintype "passive"))
    )
    (net (code "108") (name "Net-(MOTOR_12-Pad4)") (class "Default")
      (node (ref "MOTOR_12") (pin "4") (pinfunction "4_4") (pintype "passive"))
      (node (ref "MOTOR_POWER_12") (pin "6") (pinfunction "6_6") (pintype "passive"))
    )
    (net (code "109") (name "Net-(MOTOR_13-Pad1)") (class "Default")
      (node (ref "MOTOR_13") (pin "1") (pinfunction "1_1") (pintype "passive"))
      (node (ref "MOTOR_POWER_13") (pin "3") (pinfunction "3_3") (pintype "passive"))
    )
    (net (code "110") (name "Net-(MOTOR_13-Pad2)") (class "Default")
      (node (ref "MOTOR_13") (pin "2") (pinfunction "2_2") (pintype "passive"))
      (node (ref "MOTOR_POWER_13") (pin "4") (pinfunction "4_4") (pintype "passive"))
    )
    (net (code "111") (name "Net-(MOTOR_13-Pad3)") (class "Default")
      (node (ref "MOTOR_13") (pin "3") (pinfunction "3_3") (pintype "passive"))
      (node (ref "MOTOR_POWER_13") (pin "5") (pinfunction "5_5") (pintype "passive"))
    )
    (net (code "112") (name "Net-(MOTOR_13-Pad4)") (class "Default")
      (node (ref "MOTOR_13") (pin "4") (pinfunction "4_4") (pintype "passive"))
      (node (ref "MOTOR_POWER_13") (pin "6") (pinfunction "6_6") (pintype "passive"))
    )
    (net (code "113") (name "Net-(MOTOR_14-Pad1)") (class "Default")
      (node (ref "MOTOR_14") (pin "1") (pinfunction "1_1") (pintype "passive"))
      (node (ref "MOTOR_POWER_14") (pin "3") (pinfunction "3_3") (pintype "passive"))
    )
    (net (code "114") (name "Net-(MOTOR_14-Pad2)") (class "Default")
      (node (ref "MOTOR_14") (pin "2") (pinfunction "2_2") (pintype "passive"))
      (node (ref "MOTOR_POWER_14") (pin "4") (pinfunction "4_4") (pintype "passive"))
    )
    (net (code "115") (name "Net-(MOTOR_14-Pad3)") (class "Default")
      (node (ref "MOTOR_14") (pin "3") (pinfunction "3_3") (pintype "passive"))
      (node (ref "MOTOR_POWER_14") (pin "5") (pinfunction "5_5") (pintype "passive"))
    )
    (net (code "116") (name "Net-(MOTOR_14-Pad4)") (class "Default")
      (node (ref "MOTOR_14") (pin "4") (pinfunction "4_4") (pintype "passive"))
      (node (ref "MOTOR_POWER_14") (pin "6") (pinfunction "6_6") (pintype "passive"))
    )
    (net (code "117") (name "Net-(PUMP1-Pad5)") (class "Default")
      (node (ref "PUMP1") (pin "5") (pinfunction "5_5") (pintype "passive"))
      (node (ref "PUMP1") (pin "6") (pinfunction "6_6") (pintype "passive"))
    )
    (net (code "118") (name "Net-(PUMP2-Pad5)") (class "Default")
      (node (ref "PUMP2") (pin "5") (pinfunction "5_5") (pintype "passive"))
      (node (ref "PUMP2") (pin "6") (pinfunction "6_6") (pintype "passive"))
    )
    (net (code "119") (name "Net-(PUMP3-Pad5)") (class "Default")
      (node (ref "PUMP3") (pin "5") (pinfunction "5_5") (pintype "passive"))
      (node (ref "PUMP3") (pin "6") (pinfunction "6_6") (pintype "passive"))
    )
    (net (code "120") (name "Net-(PUMP4-Pad5)") (class "Default")
      (node (ref "PUMP4") (pin "5") (pinfunction "5_5") (pintype "passive"))
      (node (ref "PUMP4") (pin "6") (pinfunction "6_6") (pintype "passive"))
    )
    (net (code "121") (name "Net-(PUMP5-Pad5)") (class "Default")
      (node (ref "PUMP5") (pin "5") (pinfunction "5_5") (pintype "passive"))
      (node (ref "PUMP5") (pin "6") (pinfunction "6_6") (pintype "passive"))
    )
    (net (code "122") (name "Net-(PUMP6-Pad5)") (class "Default")
      (node (ref "PUMP6") (pin "5") (pinfunction "5_5") (pintype "passive"))
      (node (ref "PUMP6") (pin "6") (pinfunction "6_6") (pintype "passive"))
    )
    (net (code "123") (name "Net-(PUMP7-Pad5)") (class "Default")
      (node (ref "PUMP7") (pin "5") (pinfunction "5_5") (pintype "passive"))
      (node (ref "PUMP7") (pin "6") (pinfunction "6_6") (pintype "passive"))
    )
    (net (code "124") (name "Net-(PUMP8-Pad5)") (class "Default")
      (node (ref "PUMP8") (pin "5") (pinfunction "5_5") (pintype "passive"))
      (node (ref "PUMP8") (pin "6") (pinfunction "6_6") (pintype "passive"))
    )
    (net (code "125") (name "Net-(PUMP9-Pad5)") (class "Default")
      (node (ref "PUMP9") (pin "5") (pinfunction "5_5") (pintype "passive"))
      (node (ref "PUMP9") (pin "6") (pinfunction "6_6") (pintype "passive"))
    )
    (net (code "126") (name "Net-(PUMP10-Pad5)") (class "Default")
      (node (ref "PUMP10") (pin "5") (pinfunction "5_5") (pintype "passive"))
      (node (ref "PUMP10") (pin "6") (pinfunction "6_6") (pintype "passive"))
    )
    (net (code "127") (name "Net-(RIGHT_STEP-Pad3)") (class "Default")
      (node (ref "RIGHT_STEP") (pin "3") (pinfunction "3_3") (pintype "passive"))
      (node (ref "RIGHT_STEP") (pin "4") (pinfunction "4_4") (pintype "passive"))
    )
    (net (code "128") (name "Net-(Z_LEFT-Pad3)") (class "Default")
      (node (ref "Z_LEFT") (pin "3") (pinfunction "3_3") (pintype "passive"))
      (node (ref "Z_LEFT") (pin "4") (pinfunction "4_4") (pintype "passive"))
    )
    (net (code "129") (name "Net-(Z_RIGHT-Pad3)") (class "Default")
      (node (ref "Z_RIGHT") (pin "3") (pinfunction "3_3") (pintype "passive"))
      (node (ref "Z_RIGHT") (pin "4") (pinfunction "4_4") (pintype "passive"))
    )
    (net (code "130") (name "unconnected-(B1-0(RX0)-Pad0)") (class "Default")
      (node (ref "B1") (pin "0") (pinfunction "0(RX0)_0") (pintype "bidirectional"))
    )
    (net (code "131") (name "unconnected-(B1-1(TX0)-Pad1)") (class "Default")
      (node (ref "B1") (pin "1") (pinfunction "1(TX0)_1") (pintype "bidirectional"))
    )
    (net (code "132") (name "unconnected-(B1-14(TX3)-Pad14)") (class "Default")
      (node (ref "B1") (pin "14") (pinfunction "14(TX3)_14") (pintype "bidirectional"))
    )
    (net (code "133") (name "unconnected-(B1-15(RX3)-Pad15)") (class "Default")
      (node (ref "B1") (pin "15") (pinfunction "15(RX3)_15") (pintype "bidirectional"))
    )
    (net (code "134") (name "unconnected-(B1-16(TX2)-Pad16)") (class "Default")
      (node (ref "B1") (pin "16") (pinfunction "16(TX2)_16") (pintype "bidirectional"))
    )
    (net (code "135") (name "unconnected-(B1-17(RX2)-Pad17)") (class "Default")
      (node (ref "B1") (pin "17") (pinfunction "17(RX2)_17") (pintype "bidirectional"))
    )
    (net (code "136") (name "unconnected-(B1-18(TX1)-Pad18)") (class "Default")
      (node (ref "B1") (pin "18") (pinfunction "18(TX1)_18") (pintype "bidirectional"))
    )
    (net (code "137") (name "unconnected-(B1-19(RX1)-Pad19)") (class "Default")
      (node (ref "B1") (pin "19") (pinfunction "19(RX1)_19") (pintype "bidirectional"))
    )
    (net (code "138") (name "unconnected-(B1-20(SDA)-Pad20)") (class "Default")
      (node (ref "B1") (pin "20") (pinfunction "20(SDA)_20") (pintype "bidirectional"))
    )
    (net (code "139") (name "unconnected-(B1-21(SCL)-Pad21)") (class "Default")
      (node (ref "B1") (pin "21") (pinfunction "21(SCL)_21") (pintype "bidirectional"))
    )
    (net (code "140") (name "unconnected-(B1-A0(RX0)-PadA0)") (class "Default")
      (node (ref "B1") (pin "A0") (pinfunction "A0(RX0)_A0") (pintype "bidirectional"))
    )
    (net (code "141") (name "unconnected-(B1-Pad2)") (class "Default")
      (node (ref "B1") (pin "2") (pinfunction "2_2") (pintype "bidirectional"))
    )
    (net (code "142") (name "unconnected-(B1-Pad3)") (class "Default")
      (node (ref "B1") (pin "3") (pinfunction "3_3") (pintype "bidirectional"))
    )
    (net (code "143") (name "unconnected-(B1-Pad3.3V)") (class "Default")
      (node (ref "B1") (pin "3.3V") (pinfunction "3.3V_3.3V") (pintype "bidirectional"))
    )
    (net (code "144") (name "unconnected-(B1-Pad4)") (class "Default")
      (node (ref "B1") (pin "4") (pinfunction "4_4") (pintype "bidirectional"))
    )
    (net (code "145") (name "unconnected-(B1-Pad13)") (class "Default")
      (node (ref "B1") (pin "13") (pinfunction "13_13") (pintype "bidirectional"))
    )
    (net (code "146") (name "unconnected-(B1-PadAREF)") (class "Default")
      (node (ref "B1") (pin "AREF") (pinfunction "AREF_AREF") (pintype "bidirectional"))
    )
    (net (code "147") (name "unconnected-(B1-PadRESET)") (class "Default")
      (node (ref "B1") (pin "RESET") (pinfunction "RESET_RESET") (pintype "bidirectional"))
    )
    (net (code "148") (name "unconnected-(B1-PadVIN)") (class "Default")
      (node (ref "B1") (pin "VIN") (pinfunction "VIN_VIN") (pintype "bidirectional"))
    )
  )
)
